# XLR8_RX.net
KiCad netlist of a schematic drawn in EAGLE
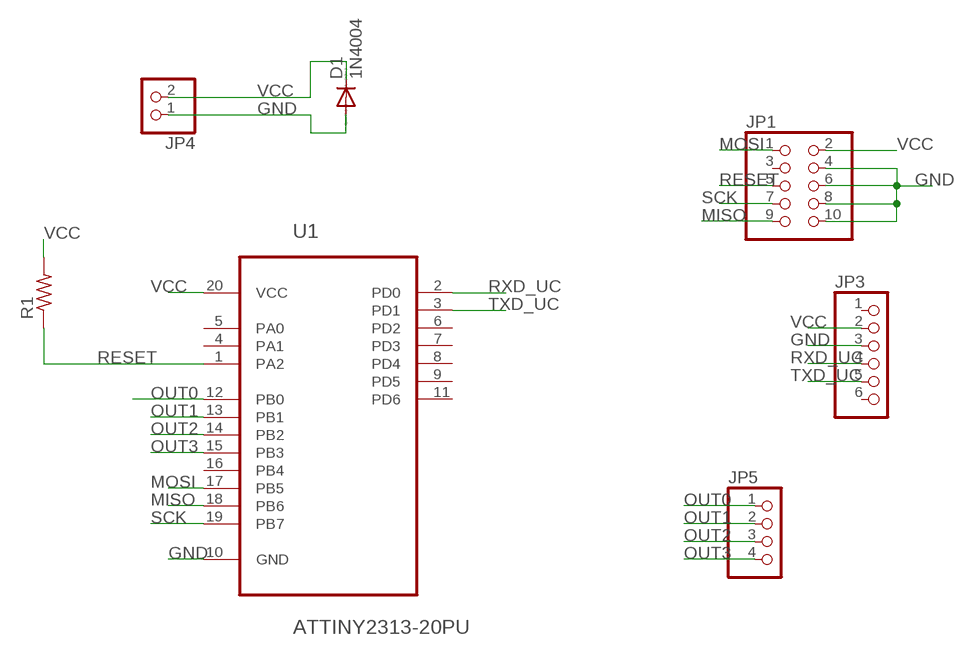
[diagram p0: schematic, sheet 1]

(export (version "E")
  (design (tool "Eeschema 10.0.6"))
  (components
    (comp (ref "D1")
      (value "1N4004")
      (footprint "eagle-import:DO41-10")
      (libsource (lib "eagle-import") (part "1N4004"))
    )
    (comp (ref "JP1")
      (value "PINHD-2X5")
      (footprint "eagle-import:2X05")
      (libsource (lib "eagle-import") (part "PINHD-2X5"))
    )
    (comp (ref "JP3")
      (value "PINHD-1X6")
      (footprint "eagle-import:1X06")
      (libsource (lib "eagle-import") (part "PINHD-1X6"))
    )
    (comp (ref "JP4")
      (value "PINHD-1X2")
      (footprint "eagle-import:1X02")
      (libsource (lib "eagle-import") (part "PINHD-1X2"))
    )
    (comp (ref "JP5")
      (value "PINHD-1X4")
      (footprint "eagle-import:1X04")
      (libsource (lib "eagle-import") (part "PINHD-1X4"))
    )
    (comp (ref "R1")
      (value "R-US_0207/10")
      (footprint "eagle-import:0207_10")
      (libsource (lib "eagle-import") (part "R-US_0207/10"))
    )
    (comp (ref "U1")
      (value "ATTINY2313-20PU")
      (footprint "eagle-import:DIP254P762X533-20")
      (libsource (lib "eagle-import") (part "ATTINY2313-20PU"))
    )
  )
  (nets
    (net (code "1") (name "/GND") (class "Default")
      (node (ref "D1") (pin "A") (pinfunction "A_A") (pintype "passive"))
      (node (ref "JP1") (pin "10") (pinfunction "10_10") (pintype "passive"))
      (node (ref "JP1") (pin "4") (pinfunction "4_4") (pintype "passive"))
      (node (ref "JP1") (pin "6") (pinfunction "6_6") (pintype "passive"))
      (node (ref "JP1") (pin "8") (pinfunction "8_8") (pintype "passive"))
      (node (ref "JP3") (pin "3") (pinfunction "3_3") (pintype "passive"))
      (node (ref "JP4") (pin "1") (pinfunction "1_1") (pintype "passive"))
      (node (ref "U1") (pin "10") (pinfunction "GND_10") (pintype "passive"))
    )
    (net (code "2") (name "/MISO") (class "Default")
      (node (ref "JP1") (pin "9") (pinfunction "9_9") (pintype "passive"))
      (node (ref "U1") (pin "18") (pinfunction "PB6_18") (pintype "bidirectional"))
    )
    (net (code "3") (name "/MOSI") (class "Default")
      (node (ref "JP1") (pin "1") (pinfunction "1_1") (pintype "passive"))
      (node (ref "U1") (pin "17") (pinfunction "PB5_17") (pintype "bidirectional"))
    )
    (net (code "4") (name "/OUT0") (class "Default")
      (node (ref "JP5") (pin "1") (pinfunction "1_1") (pintype "passive"))
      (node (ref "U1") (pin "12") (pinfunction "PB0_12") (pintype "bidirectional"))
    )
    (net (code "5") (name "/OUT1") (class "Default")
      (node (ref "JP5") (pin "2") (pinfunction "2_2") (pintype "passive"))
      (node (ref "U1") (pin "13") (pinfunction "PB1_13") (pintype "bidirectional"))
    )
    (net (code "6") (name "/OUT2") (class "Default")
      (node (ref "JP5") (pin "3") (pinfunction "3_3") (pintype "passive"))
      (node (ref "U1") (pin "14") (pinfunction "PB2_14") (pintype "bidirectional"))
    )
    (net (code "7") (name "/OUT3") (class "Default")
      (node (ref "JP5") (pin "4") (pinfunction "4_4") (pintype "passive"))
      (node (ref "U1") (pin "15") (pinfunction "PB3_15") (pintype "bidirectional"))
    )
    (net (code "8") (name "/RESET") (class "Default")
      (node (ref "JP1") (pin "5") (pinfunction "5_5") (pintype "passive"))
      (node (ref "R1") (pin "1") (pinfunction "1_1") (pintype "passive"))
      (node (ref "U1") (pin "1") (pinfunction "PA2_1") (pintype "bidirectional"))
    )
    (net (code "9") (name "/RXD_UC") (class "Default")
      (node (ref "JP3") (pin "4") (pinfunction "4_4") (pintype "passive"))
      (node (ref "U1") (pin "2") (pinfunction "PD0_2") (pintype "bidirectional"))
    )
    (net (code "10") (name "/SCK") (class "Default")
      (node (ref "JP1") (pin "7") (pinfunction "7_7") (pintype "passive"))
      (node (ref "U1") (pin "19") (pinfunction "PB7_19") (pintype "bidirectional"))
    )
    (net (code "11") (name "/TXD_UC") (class "Default")
      (node (ref "JP3") (pin "5") (pinfunction "5_5") (pintype "passive"))
      (node (ref "U1") (pin "3") (pinfunction "PD1_3") (pintype "bidirectional"))
    )
    (net (code "12") (name "/VCC") (class "Default")
      (node (ref "D1") (pin "C") (pinfunction "C_C") (pintype "passive"))
      (node (ref "JP1") (pin "2") (pinfunction "2_2") (pintype "passive"))
      (node (ref "JP3") (pin "2") (pinfunction "2_2") (pintype "passive"))
      (node (ref "JP4") (pin "2") (pinfunction "2_2") (pintype "passive"))
      (node (ref "R1") (pin "2") (pinfunction "2_2") (pintype "passive"))
      (node (ref "U1") (pin "20") (pinfunction "VCC_20") (pintype "power_in"))
    )
    (net (code "13") (name "unconnected-(JP1-Pad3)") (class "Default")
      (node (ref "JP1") (pin "3") (pinfunction "3_3") (pintype "passive"))
    )
    (net (code "14") (name "unconnected-(JP3-Pad1)") (class "Default")
      (node (ref "JP3") (pin "1") (pinfunction "1_1") (pintype "passive"))
    )
    (net (code "15") (name "unconnected-(JP3-Pad6)") (class "Default")
      (node (ref "JP3") (pin "6") (pinfunction "6_6") (pintype "passive"))
    )
    (net (code "16") (name "unconnected-(U1-PA0-Pad5)") (class "Default")
      (node (ref "U1") (pin "5") (pinfunction "PA0_5") (pintype "bidirectional"))
    )
    (net (code "17") (name "unconnected-(U1-PA1-Pad4)") (class "Default")
      (node (ref "U1") (pin "4") (pinfunction "PA1_4") (pintype "bidirectional"))
    )
    (net (code "18") (name "unconnected-(U1-PB4-Pad16)") (class "Default")
      (node (ref "U1") (pin "16") (pinfunction "PB4_16") (pintype "bidirectional"))
    )
    (net (code "19") (name "unconnected-(U1-PD2-Pad6)") (class "Default")
      (node (ref "U1") (pin "6") (pinfunction "PD2_6") (pintype "bidirectional"))
    )
    (net (code "20") (name "unconnected-(U1-PD3-Pad7)") (class "Default")
      (node (ref "U1") (pin "7") (pinfunction "PD3_7") (pintype "bidirectional"))
    )
    (net (code "21") (name "unconnected-(U1-PD4-Pad8)") (class "Default")
      (node (ref "U1") (pin "8") (pinfunction "PD4_8") (pintype "bidirectional"))
    )
    (net (code "22") (name "unconnected-(U1-PD5-Pad9)") (class "Default")
      (node (ref "U1") (pin "9") (pinfunction "PD5_9") (pintype "bidirectional"))
    )
    (net (code "23") (name "unconnected-(U1-PD6-Pad11)") (class "Default")
      (node (ref "U1") (pin "11") (pinfunction "PD6_11") (pintype "bidirectional"))
    )
  )
)
